# femtoBeacon_board_nRF52832_BT4_2_r1_0_0.net
KiCad netlist of a schematic drawn in EAGLE
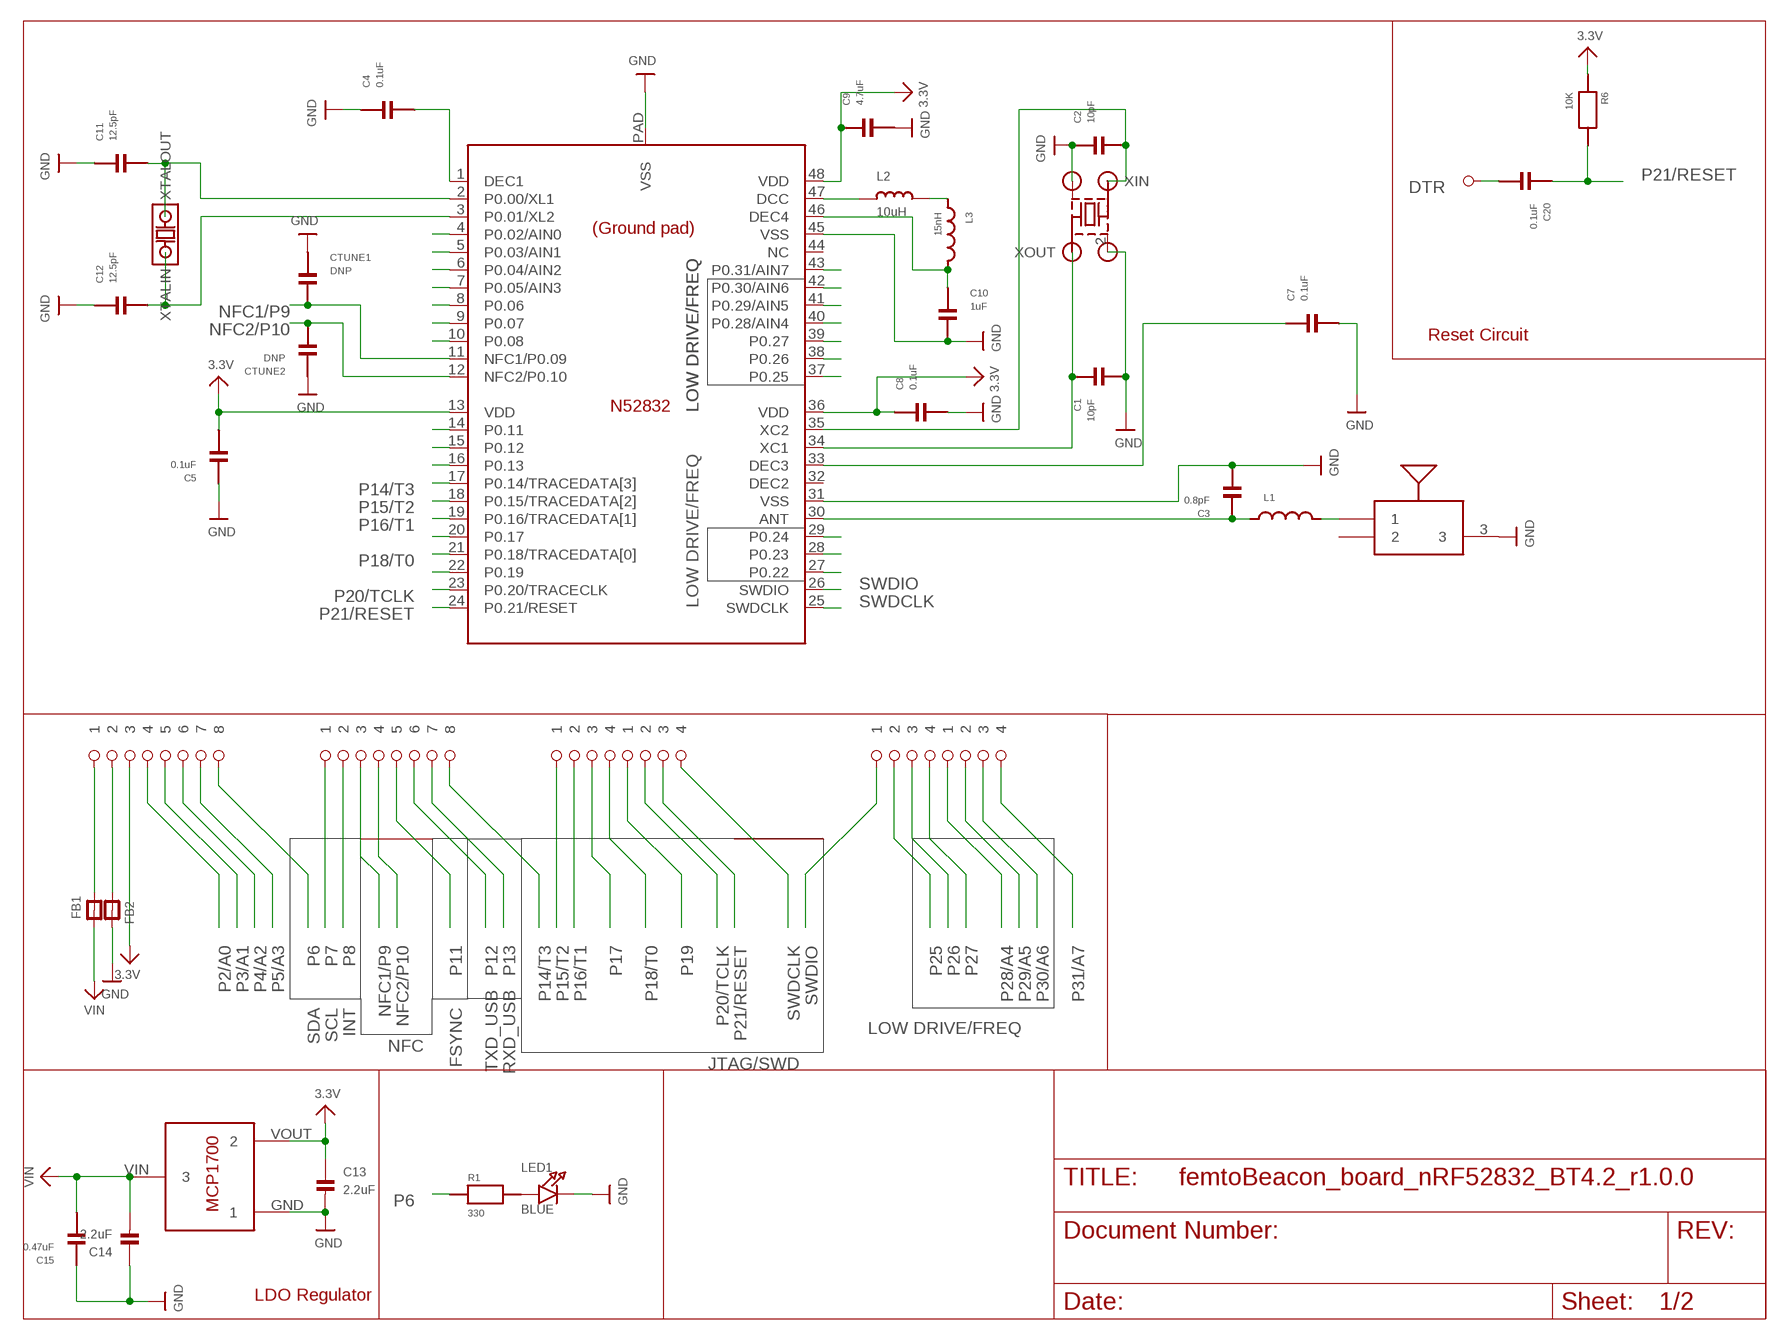
[diagram p0: schematic, sheet 1]
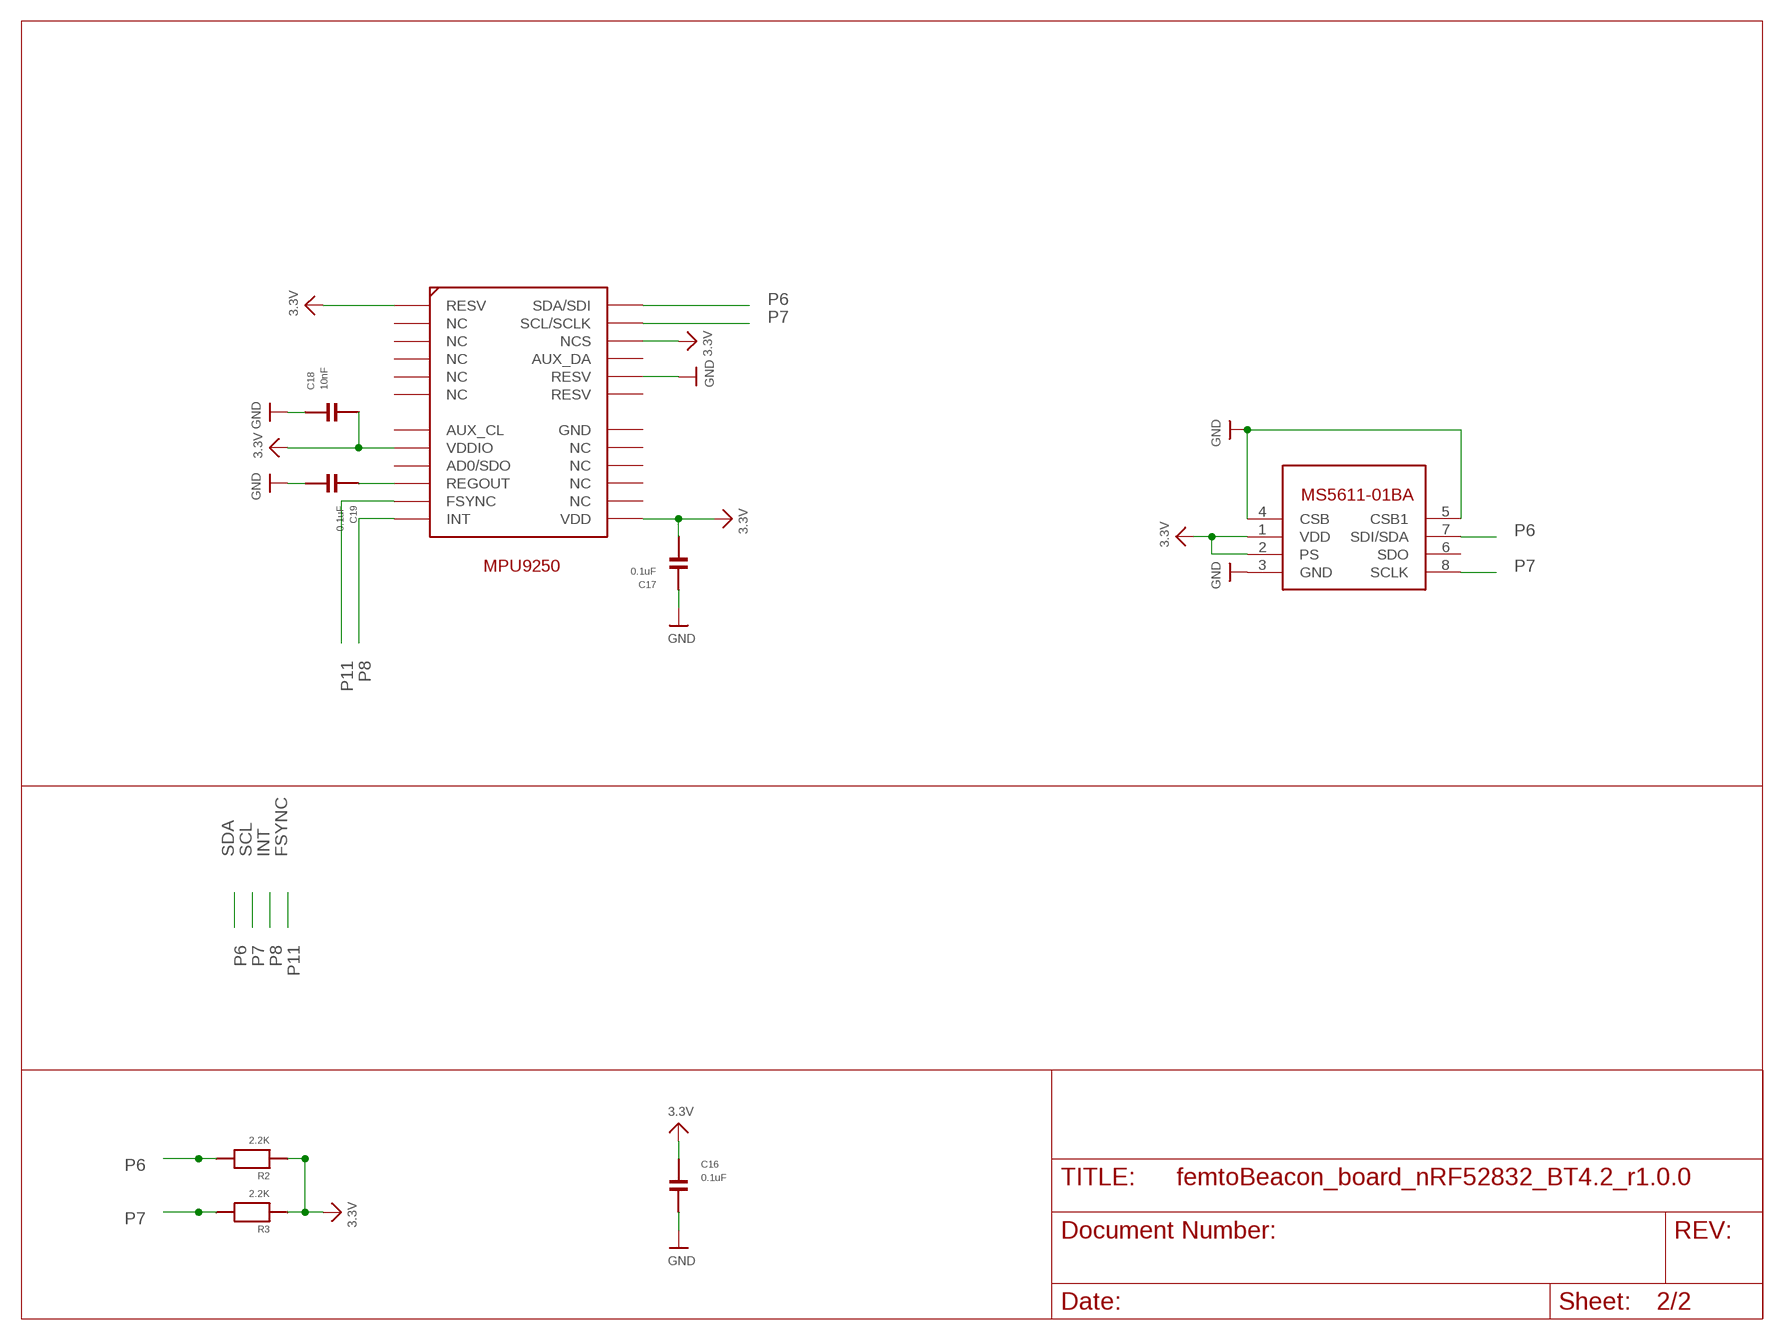
[diagram p1: schematic, sheet 2]

(export (version "E")
  (design (tool "Eeschema 10.0.6"))
  (components
    (comp (ref "BARO1")
      (value "MS5611-01BA03")
      (footprint "eagle-import:MS5611-01BA03")
      (libsource (lib "eagle-import") (part "MS5611-01BA03"))
    )
    (comp (ref "C16")
      (value "0.1uF")
      (footprint "eagle-import:PART")
      (libsource (lib "eagle-import") (part "CAPACITOR_0201"))
    )
    (comp (ref "C17")
      (value "0.1uF")
      (footprint "eagle-import:PART")
      (libsource (lib "eagle-import") (part "CAPACITOR_0201"))
    )
    (comp (ref "C18")
      (value "10nF")
      (footprint "eagle-import:PART")
      (libsource (lib "eagle-import") (part "CAPACITOR_0201"))
    )
    (comp (ref "C19")
      (value "0.1uF")
      (footprint "eagle-import:PART")
      (libsource (lib "eagle-import") (part "CAPACITOR_0201"))
    )
    (comp (ref "IMU1")
      (value "MPU-9250")
      (footprint "eagle-import:QFN_3X3MM")
      (libsource (lib "eagle-import") (part "MPU-9250"))
    )
    (comp (ref "R2")
      (value "2.2K")
      (footprint "eagle-import:PART")
      (libsource (lib "eagle-import") (part "RESISTOR_0201"))
    )
    (comp (ref "R3")
      (value "2.2K")
      (footprint "eagle-import:PART")
      (libsource (lib "eagle-import") (part "RESISTOR_0201"))
    )
    (comp (ref "ANTBAR")
      (value "PULSE_ANT_2.4GHZ")
      (footprint "eagle-import:ANT_BAR")
      (libsource (lib "eagle-import") (part "PULSE_ANT_2.4GHZ"))
    )
    (comp (ref "C1")
      (value "10pF")
      (footprint "eagle-import:PART")
      (libsource (lib "eagle-import") (part "CAPACITOR_0201"))
    )
    (comp (ref "C2")
      (value "10pF")
      (footprint "eagle-import:PART")
      (libsource (lib "eagle-import") (part "CAPACITOR_0201"))
    )
    (comp (ref "C3")
      (value "0.8pF")
      (footprint "eagle-import:PART")
      (libsource (lib "eagle-import") (part "CAPACITOR_0201"))
    )
    (comp (ref "C4")
      (value "0.1uF")
      (footprint "eagle-import:PART")
      (libsource (lib "eagle-import") (part "CAPACITOR_0201"))
    )
    (comp (ref "C5")
      (value "0.1uF")
      (footprint "eagle-import:PART")
      (libsource (lib "eagle-import") (part "CAPACITOR_0201"))
    )
    (comp (ref "C7")
      (value "0.1uF")
      (footprint "eagle-import:PART")
      (libsource (lib "eagle-import") (part "CAPACITOR_0201"))
    )
    (comp (ref "C8")
      (value "0.1uF")
      (footprint "eagle-import:PART")
      (libsource (lib "eagle-import") (part "CAPACITOR_0201"))
    )
    (comp (ref "C9")
      (value "4.7uF")
      (footprint "eagle-import:PART")
      (libsource (lib "eagle-import") (part "CAPACITOR_0201"))
    )
    (comp (ref "C10")
      (value "1uF")
      (footprint "eagle-import:PART")
      (libsource (lib "eagle-import") (part "CAPACITOR_0201"))
    )
    (comp (ref "C11")
      (value "12.5pF")
      (footprint "eagle-import:PART")
      (libsource (lib "eagle-import") (part "CAPACITOR_0201"))
    )
    (comp (ref "C12")
      (value "12.5pF")
      (footprint "eagle-import:PART")
      (libsource (lib "eagle-import") (part "CAPACITOR_0201"))
    )
    (comp (ref "C13")
      (value "2.2uF")
      (footprint "eagle-import:_0402MP")
      (libsource (lib "eagle-import") (part "CAP_CERAMIC_0402MP"))
    )
    (comp (ref "C14")
      (value "2.2uF")
      (footprint "eagle-import:_0402MP")
      (libsource (lib "eagle-import") (part "CAP_CERAMIC_0402MP"))
    )
    (comp (ref "C15")
      (value "0.47uF")
      (footprint "eagle-import:PART")
      (libsource (lib "eagle-import") (part "CAPACITOR_0201"))
    )
    (comp (ref "C20")
      (value "0.1uF")
      (footprint "eagle-import:PART")
      (libsource (lib "eagle-import") (part "CAPACITOR_0201"))
    )
    (comp (ref "CTUNE1")
      (value "DNP")
      (footprint "eagle-import:PART")
      (libsource (lib "eagle-import") (part "CAPACITOR_0201"))
    )
    (comp (ref "CTUNE2")
      (value "DNP")
      (footprint "eagle-import:PART")
      (libsource (lib "eagle-import") (part "CAPACITOR_0201"))
    )
    (comp (ref "FB1")
      (value "FERRITE_0603MP")
      (footprint "eagle-import:_0603MP")
      (libsource (lib "eagle-import") (part "FERRITE_0603MP"))
    )
    (comp (ref "FB2")
      (value "FERRITE_0603MP")
      (footprint "eagle-import:_0603MP")
      (libsource (lib "eagle-import") (part "FERRITE_0603MP"))
    )
    (comp (ref "IC1")
      (value "NRF52832_QFN48")
      (footprint "eagle-import:QFN48")
      (libsource (lib "eagle-import") (part "NRF52832_QFN48"))
    )
    (comp (ref "L1")
      (value "INDUCTOR_FIXED_0201")
      (footprint "eagle-import:PART")
      (libsource (lib "eagle-import") (part "INDUCTOR_FIXED_0201"))
    )
    (comp (ref "L2")
      (value "10uH")
      (footprint "eagle-import:_0603MP")
      (libsource (lib "eagle-import") (part "INDUCTOR_0603MP"))
    )
    (comp (ref "L3")
      (value "15nH")
      (footprint "eagle-import:PART")
      (libsource (lib "eagle-import") (part "INDUCTOR_FIXED_0201"))
    )
    (comp (ref "LED1")
      (value "BLUE")
      (footprint "eagle-import:CHIPLED_0603_NOOUTLINE")
      (libsource (lib "eagle-import") (part "LED0603_NOOUTLINE"))
    )
    (comp (ref "PIN4")
      (value "1X1_ROUND")
      (footprint "eagle-import:1X1_ROUND")
      (libsource (lib "eagle-import") (part "1X1_ROUND"))
    )
    (comp (ref "PINS1")
      (value "1X8_ROUND")
      (footprint "eagle-import:1X8_ROUND")
      (libsource (lib "eagle-import") (part "1X8_ROUND"))
    )
    (comp (ref "PINS2")
      (value "1X8_ROUND")
      (footprint "eagle-import:1X8_ROUND")
      (libsource (lib "eagle-import") (part "1X8_ROUND"))
    )
    (comp (ref "PINS3A")
      (value "1X4_ROUND")
      (footprint "eagle-import:1X4_ROUND")
      (libsource (lib "eagle-import") (part "1X4_ROUND"))
    )
    (comp (ref "PINS3B")
      (value "1X4_ROUND")
      (footprint "eagle-import:1X4_ROUND")
      (libsource (lib "eagle-import") (part "1X4_ROUND"))
    )
    (comp (ref "PINS4A")
      (value "1X4_ROUND")
      (footprint "eagle-import:1X4_ROUND")
      (libsource (lib "eagle-import") (part "1X4_ROUND"))
    )
    (comp (ref "PINS4B")
      (value "1X4_ROUND")
      (footprint "eagle-import:1X4_ROUND")
      (libsource (lib "eagle-import") (part "1X4_ROUND"))
    )
    (comp (ref "R1")
      (value "330")
      (footprint "eagle-import:PART")
      (libsource (lib "eagle-import") (part "RESISTOR_0201"))
    )
    (comp (ref "R6")
      (value "10K")
      (footprint "eagle-import:PART")
      (libsource (lib "eagle-import") (part "RESISTOR_0201"))
    )
    (comp (ref "U$4")
      (value "MCP1700T-3302E/TT")
      (footprint "eagle-import:MCP1700T-3302E_TT")
      (libsource (lib "eagle-import") (part "MCP1700T-3302E/TT"))
    )
    (comp (ref "U$53")
      (value "ABS06-107-32.768KHZ-T")
      (footprint "eagle-import:ABS06-107-32.768KHZ-T")
      (libsource (lib "eagle-import") (part "ABS06-107-32.768KHZ-T"))
    )
    (comp (ref "XTAL")
      (value "32MHz")
      (footprint "eagle-import:ABM11")
      (libsource (lib "eagle-import") (part "ABM11-32.000MHZ-D2X-T3"))
    )
  )
  (nets
    (net (code "1") (name "3.3V") (class "Default")
      (node (ref "BARO1") (pin "1") (pinfunction "VDD_1") (pintype "bidirectional"))
      (node (ref "BARO1") (pin "2") (pinfunction "PS_2") (pintype "bidirectional"))
      (node (ref "C13") (pin "1") (pinfunction "P$1_1") (pintype "passive"))
      (node (ref "C16") (pin "1") (pinfunction "P$1_1") (pintype "bidirectional"))
      (node (ref "C17") (pin "2") (pinfunction "P$2_2") (pintype "bidirectional"))
      (node (ref "C18") (pin "2") (pinfunction "P$2_2") (pintype "bidirectional"))
      (node (ref "C5") (pin "2") (pinfunction "P$2_2") (pintype "bidirectional"))
      (node (ref "C8") (pin "1") (pinfunction "P$1_1") (pintype "bidirectional"))
      (node (ref "C9") (pin "1") (pinfunction "P$1_1") (pintype "bidirectional"))
      (node (ref "IC1") (pin "13") (pinfunction "VDD_13") (pintype "bidirectional"))
      (node (ref "IC1") (pin "36") (pinfunction "VDD_36") (pintype "bidirectional"))
      (node (ref "IC1") (pin "48") (pinfunction "VDD_48") (pintype "bidirectional"))
      (node (ref "IMU1") (pin "P$1") (pinfunction "RESV_P$1") (pintype "bidirectional"))
      (node (ref "IMU1") (pin "P$13") (pinfunction "VDD_P$13") (pintype "bidirectional"))
      (node (ref "IMU1") (pin "P$22") (pinfunction "NCS_P$22") (pintype "bidirectional"))
      (node (ref "IMU1") (pin "P$8") (pinfunction "VDDIO_P$8") (pintype "bidirectional"))
      (node (ref "PINS1") (pin "P$3") (pinfunction "3_P$3") (pintype "bidirectional"))
      (node (ref "R2") (pin "1") (pinfunction "1_1") (pintype "bidirectional"))
      (node (ref "R3") (pin "1") (pinfunction "1_1") (pintype "bidirectional"))
      (node (ref "R6") (pin "1") (pinfunction "1_1") (pintype "bidirectional"))
      (node (ref "U$4") (pin "VOUT") (pinfunction "2_VOUT") (pintype "bidirectional"))
    )
    (net (code "2") (name "DTR") (class "Default")
      (node (ref "C20") (pin "2") (pinfunction "P$2_2") (pintype "bidirectional"))
      (node (ref "PIN4") (pin "P$1") (pinfunction "1_P$1") (pintype "bidirectional"))
    )
    (net (code "3") (name "GND") (class "Default")
      (node (ref "ANTBAR") (pin "3") (pinfunction "3_3") (pintype "bidirectional"))
      (node (ref "BARO1") (pin "3") (pinfunction "GND_3") (pintype "bidirectional"))
      (node (ref "BARO1") (pin "4") (pinfunction "CSB_4") (pintype "bidirectional"))
      (node (ref "BARO1") (pin "5") (pinfunction "CSB1_5") (pintype "bidirectional"))
      (node (ref "C1") (pin "2") (pinfunction "P$2_2") (pintype "bidirectional"))
      (node (ref "C10") (pin "2") (pinfunction "P$2_2") (pintype "bidirectional"))
      (node (ref "C11") (pin "1") (pinfunction "P$1_1") (pintype "bidirectional"))
      (node (ref "C12") (pin "1") (pinfunction "P$1_1") (pintype "bidirectional"))
      (node (ref "C13") (pin "2") (pinfunction "P$2_2") (pintype "passive"))
      (node (ref "C14") (pin "1") (pinfunction "P$1_1") (pintype "passive"))
      (node (ref "C15") (pin "1") (pinfunction "P$1_1") (pintype "bidirectional"))
      (node (ref "C16") (pin "2") (pinfunction "P$2_2") (pintype "bidirectional"))
      (node (ref "C17") (pin "1") (pinfunction "P$1_1") (pintype "bidirectional"))
      (node (ref "C18") (pin "1") (pinfunction "P$1_1") (pintype "bidirectional"))
      (node (ref "C19") (pin "2") (pinfunction "P$2_2") (pintype "bidirectional"))
      (node (ref "C2") (pin "1") (pinfunction "P$1_1") (pintype "bidirectional"))
      (node (ref "C3") (pin "2") (pinfunction "P$2_2") (pintype "bidirectional"))
      (node (ref "C4") (pin "1") (pinfunction "P$1_1") (pintype "bidirectional"))
      (node (ref "C5") (pin "1") (pinfunction "P$1_1") (pintype "bidirectional"))
      (node (ref "C7") (pin "2") (pinfunction "P$2_2") (pintype "bidirectional"))
      (node (ref "C8") (pin "2") (pinfunction "P$2_2") (pintype "bidirectional"))
      (node (ref "C9") (pin "2") (pinfunction "P$2_2") (pintype "bidirectional"))
      (node (ref "CTUNE1") (pin "1") (pinfunction "P$1_1") (pintype "bidirectional"))
      (node (ref "CTUNE2") (pin "1") (pinfunction "P$1_1") (pintype "bidirectional"))
      (node (ref "FB2") (pin "2") (pinfunction "P$2_2") (pintype "passive"))
      (node (ref "IC1") (pin "31") (pinfunction "VSS_31") (pintype "bidirectional"))
      (node (ref "IC1") (pin "45") (pinfunction "VSS_45") (pintype "bidirectional"))
      (node (ref "IC1") (pin "PAD") (pinfunction "VSS_PAD") (pintype "bidirectional"))
      (node (ref "IMU1") (pin "P$20") (pinfunction "RESV_P$20") (pintype "bidirectional"))
      (node (ref "LED1") (pin "C") (pinfunction "C_C") (pintype "passive"))
      (node (ref "U$4") (pin "GND") (pinfunction "1_GND") (pintype "bidirectional"))
      (node (ref "XTAL") (pin "2") (pinfunction "GND_2") (pintype "bidirectional"))
      (node (ref "XTAL") (pin "4") (pinfunction "GND_4") (pintype "bidirectional"))
    )
    (net (code "4") (name "NFC1{slash}P9") (class "Default")
      (node (ref "CTUNE1") (pin "2") (pinfunction "P$2_2") (pintype "bidirectional"))
      (node (ref "IC1") (pin "11") (pinfunction "NFC1/P0.09_11") (pintype "bidirectional"))
      (node (ref "PINS2") (pin "P$3") (pinfunction "3_P$3") (pintype "bidirectional"))
    )
    (net (code "5") (name "NFC2{slash}P10") (class "Default")
      (node (ref "CTUNE2") (pin "2") (pinfunction "P$2_2") (pintype "bidirectional"))
      (node (ref "IC1") (pin "12") (pinfunction "NFC2/P0.10_12") (pintype "bidirectional"))
      (node (ref "PINS2") (pin "P$4") (pinfunction "4_P$4") (pintype "bidirectional"))
    )
    (net (code "6") (name "Net-(C1-P$1)") (class "Default")
      (node (ref "C1") (pin "1") (pinfunction "P$1_1") (pintype "bidirectional"))
      (node (ref "IC1") (pin "34") (pinfunction "XC1_34") (pintype "bidirectional"))
      (node (ref "XTAL") (pin "3") (pinfunction "XOUT_3") (pintype "bidirectional"))
    )
    (net (code "7") (name "Net-(C2-P$2)") (class "Default")
      (node (ref "C2") (pin "2") (pinfunction "P$2_2") (pintype "bidirectional"))
      (node (ref "IC1") (pin "35") (pinfunction "XC2_35") (pintype "bidirectional"))
      (node (ref "XTAL") (pin "1") (pinfunction "XIN_1") (pintype "bidirectional"))
    )
    (net (code "8") (name "Net-(C3-P$1)") (class "Default")
      (node (ref "C3") (pin "1") (pinfunction "P$1_1") (pintype "bidirectional"))
      (node (ref "IC1") (pin "30") (pinfunction "ANT_30") (pintype "bidirectional"))
      (node (ref "L1") (pin "1") (pinfunction "P$1_1") (pintype "bidirectional"))
    )
    (net (code "9") (name "Net-(C4-P$2)") (class "Default")
      (node (ref "C4") (pin "2") (pinfunction "P$2_2") (pintype "bidirectional"))
      (node (ref "IC1") (pin "1") (pinfunction "DEC1_1") (pintype "bidirectional"))
    )
    (net (code "10") (name "Net-(C7-P$1)") (class "Default")
      (node (ref "C7") (pin "1") (pinfunction "P$1_1") (pintype "bidirectional"))
      (node (ref "IC1") (pin "33") (pinfunction "DEC3_33") (pintype "bidirectional"))
    )
    (net (code "11") (name "Net-(C10-P$1)") (class "Default")
      (node (ref "C10") (pin "1") (pinfunction "P$1_1") (pintype "bidirectional"))
      (node (ref "IC1") (pin "46") (pinfunction "DEC4_46") (pintype "bidirectional"))
      (node (ref "L3") (pin "2") (pinfunction "P$2_2") (pintype "bidirectional"))
    )
    (net (code "12") (name "Net-(C11-P$2)") (class "Default")
      (node (ref "C11") (pin "2") (pinfunction "P$2_2") (pintype "bidirectional"))
      (node (ref "IC1") (pin "2") (pinfunction "P0.00/XL1_2") (pintype "bidirectional"))
      (node (ref "U$53") (pin "2") (pinfunction "XTALOUT_2") (pintype "bidirectional"))
    )
    (net (code "13") (name "Net-(C12-P$2)") (class "Default")
      (node (ref "C12") (pin "2") (pinfunction "P$2_2") (pintype "bidirectional"))
      (node (ref "IC1") (pin "3") (pinfunction "P0.01/XL2_3") (pintype "bidirectional"))
      (node (ref "U$53") (pin "1") (pinfunction "XTALIN_1") (pintype "bidirectional"))
    )
    (net (code "14") (name "Net-(C19-P$1)") (class "Default")
      (node (ref "C19") (pin "1") (pinfunction "P$1_1") (pintype "bidirectional"))
      (node (ref "IMU1") (pin "P$10") (pinfunction "REGOUT_P$10") (pintype "bidirectional"))
    )
    (net (code "15") (name "Net-(FB1-P$2)") (class "Default")
      (node (ref "FB1") (pin "2") (pinfunction "P$2_2") (pintype "passive"))
      (node (ref "PINS1") (pin "P$1") (pinfunction "1_P$1") (pintype "bidirectional"))
    )
    (net (code "16") (name "Net-(FB2-P$1)") (class "Default")
      (node (ref "FB2") (pin "1") (pinfunction "P$1_1") (pintype "passive"))
      (node (ref "PINS1") (pin "P$2") (pinfunction "2_P$2") (pintype "bidirectional"))
    )
    (net (code "17") (name "Net-(IC1-DCC)") (class "Default")
      (node (ref "IC1") (pin "47") (pinfunction "DCC_47") (pintype "bidirectional"))
      (node (ref "L2") (pin "1") (pinfunction "1_1") (pintype "passive"))
    )
    (net (code "18") (name "Net-(L1-P$2)") (class "Default")
      (node (ref "ANTBAR") (pin "1") (pinfunction "1_1") (pintype "bidirectional"))
      (node (ref "L1") (pin "2") (pinfunction "P$2_2") (pintype "bidirectional"))
    )
    (net (code "19") (name "Net-(L3-P$1)") (class "Default")
      (node (ref "L2") (pin "2") (pinfunction "2_2") (pintype "passive"))
      (node (ref "L3") (pin "1") (pinfunction "P$1_1") (pintype "bidirectional"))
    )
    (net (code "20") (name "Net-(LED1-PadA)") (class "Default")
      (node (ref "LED1") (pin "A") (pinfunction "A_A") (pintype "passive"))
      (node (ref "R1") (pin "2") (pinfunction "2_2") (pintype "bidirectional"))
    )
    (net (code "21") (name "P2{slash}A0") (class "Default")
      (node (ref "IC1") (pin "4") (pinfunction "P0.02/AIN0_4") (pintype "bidirectional"))
      (node (ref "PINS1") (pin "P$4") (pinfunction "4_P$4") (pintype "bidirectional"))
    )
    (net (code "22") (name "P3{slash}A1") (class "Default")
      (node (ref "IC1") (pin "5") (pinfunction "P0.03/AIN1_5") (pintype "bidirectional"))
      (node (ref "PINS1") (pin "P$5") (pinfunction "5_P$5") (pintype "bidirectional"))
    )
    (net (code "23") (name "P4{slash}A2") (class "Default")
      (node (ref "IC1") (pin "6") (pinfunction "P0.04/AIN2_6") (pintype "bidirectional"))
      (node (ref "PINS1") (pin "P$6") (pinfunction "6_P$6") (pintype "bidirectional"))
    )
    (net (code "24") (name "P5{slash}A3") (class "Default")
      (node (ref "IC1") (pin "7") (pinfunction "P0.05/AIN3_7") (pintype "bidirectional"))
      (node (ref "PINS1") (pin "P$7") (pinfunction "7_P$7") (pintype "bidirectional"))
    )
    (net (code "25") (name "P6") (class "Default")
      (node (ref "BARO1") (pin "7") (pinfunction "SDI/SDA_7") (pintype "bidirectional"))
      (node (ref "IC1") (pin "8") (pinfunction "P0.06_8") (pintype "bidirectional"))
      (node (ref "IMU1") (pin "P$24") (pinfunction "SDA/SDI_P$24") (pintype "bidirectional"))
      (node (ref "PINS1") (pin "P$8") (pinfunction "8_P$8") (pintype "bidirectional"))
      (node (ref "R1") (pin "1") (pinfunction "1_1") (pintype "bidirectional"))
      (node (ref "R2") (pin "2") (pinfunction "2_2") (pintype "bidirectional"))
    )
    (net (code "26") (name "P7") (class "Default")
      (node (ref "BARO1") (pin "8") (pinfunction "SCLK_8") (pintype "bidirectional"))
      (node (ref "IC1") (pin "9") (pinfunction "P0.07_9") (pintype "bidirectional"))
      (node (ref "IMU1") (pin "P$23") (pinfunction "SCL/SCLK_P$23") (pintype "bidirectional"))
      (node (ref "PINS2") (pin "P$1") (pinfunction "1_P$1") (pintype "bidirectional"))
      (node (ref "R3") (pin "2") (pinfunction "2_2") (pintype "bidirectional"))
    )
    (net (code "27") (name "P8") (class "Default")
      (node (ref "IC1") (pin "10") (pinfunction "P0.08_10") (pintype "bidirectional"))
      (node (ref "IMU1") (pin "P$12") (pinfunction "INT_P$12") (pintype "bidirectional"))
      (node (ref "PINS2") (pin "P$2") (pinfunction "2_P$2") (pintype "bidirectional"))
    )
    (net (code "28") (name "P11") (class "Default")
      (node (ref "IC1") (pin "14") (pinfunction "P0.11_14") (pintype "bidirectional"))
      (node (ref "IMU1") (pin "P$11") (pinfunction "FSYNC_P$11") (pintype "bidirectional"))
      (node (ref "PINS2") (pin "P$5") (pinfunction "5_P$5") (pintype "bidirectional"))
    )
    (net (code "29") (name "P12") (class "Default")
      (node (ref "IC1") (pin "15") (pinfunction "P0.12_15") (pintype "bidirectional"))
      (node (ref "PINS2") (pin "P$6") (pinfunction "6_P$6") (pintype "bidirectional"))
    )
    (net (code "30") (name "P13") (class "Default")
      (node (ref "IC1") (pin "16") (pinfunction "P0.13_16") (pintype "bidirectional"))
      (node (ref "PINS2") (pin "P$7") (pinfunction "7_P$7") (pintype "bidirectional"))
    )
    (net (code "31") (name "P14{slash}T3") (class "Default")
      (node (ref "IC1") (pin "17") (pinfunction "P0.14/TRACEDATA[3]_17") (pintype "bidirectional"))
      (node (ref "PINS2") (pin "P$8") (pinfunction "8_P$8") (pintype "bidirectional"))
    )
    (net (code "32") (name "P15{slash}T2") (class "Default")
      (node (ref "IC1") (pin "18") (pinfunction "P0.15/TRACEDATA[2]_18") (pintype "bidirectional"))
      (node (ref "PINS3A") (pin "P$1") (pinfunction "1_P$1") (pintype "bidirectional"))
    )
    (net (code "33") (name "P16{slash}T1") (class "Default")
      (node (ref "IC1") (pin "19") (pinfunction "P0.16/TRACEDATA[1]_19") (pintype "bidirectional"))
      (node (ref "PINS3A") (pin "P$2") (pinfunction "2_P$2") (pintype "bidirectional"))
    )
    (net (code "34") (name "P17") (class "Default")
      (node (ref "IC1") (pin "20") (pinfunction "P0.17_20") (pintype "bidirectional"))
      (node (ref "PINS3A") (pin "P$3") (pinfunction "3_P$3") (pintype "bidirectional"))
    )
    (net (code "35") (name "P18{slash}T0") (class "Default")
      (node (ref "IC1") (pin "21") (pinfunction "P0.18/TRACEDATA[0]_21") (pintype "bidirectional"))
      (node (ref "PINS3A") (pin "P$4") (pinfunction "4_P$4") (pintype "bidirectional"))
    )
    (net (code "36") (name "P19") (class "Default")
      (node (ref "IC1") (pin "22") (pinfunction "P0.19_22") (pintype "bidirectional"))
      (node (ref "PINS3B") (pin "P$1") (pinfunction "1_P$1") (pintype "bidirectional"))
    )
    (net (code "37") (name "P20{slash}TCLK") (class "Default")
      (node (ref "IC1") (pin "23") (pinfunction "P0.20/TRACECLK_23") (pintype "bidirectional"))
      (node (ref "PINS3B") (pin "P$2") (pinfunction "2_P$2") (pintype "bidirectional"))
    )
    (net (code "38") (name "P21{slash}RESET") (class "Default")
      (node (ref "C20") (pin "1") (pinfunction "P$1_1") (pintype "bidirectional"))
      (node (ref "IC1") (pin "24") (pinfunction "P0.21/RESET_24") (pintype "bidirectional"))
      (node (ref "PINS3B") (pin "P$3") (pinfunction "3_P$3") (pintype "bidirectional"))
      (node (ref "R6") (pin "2") (pinfunction "2_2") (pintype "bidirectional"))
    )
    (net (code "39") (name "P25") (class "Default")
      (node (ref "IC1") (pin "37") (pinfunction "P0.25_37") (pintype "bidirectional"))
      (node (ref "PINS4A") (pin "P$2") (pinfunction "2_P$2") (pintype "bidirectional"))
    )
    (net (code "40") (name "P26") (class "Default")
      (node (ref "IC1") (pin "38") (pinfunction "P0.26_38") (pintype "bidirectional"))
      (node (ref "PINS4A") (pin "P$3") (pinfunction "3_P$3") (pintype "bidirectional"))
    )
    (net (code "41") (name "P27") (class "Default")
      (node (ref "IC1") (pin "39") (pinfunction "P0.27_39") (pintype "bidirectional"))
      (node (ref "PINS4A") (pin "P$4") (pinfunction "4_P$4") (pintype "bidirectional"))
    )
    (net (code "42") (name "P28{slash}A4") (class "Default")
      (node (ref "IC1") (pin "40") (pinfunction "P0.28/AIN4_40") (pintype "bidirectional"))
      (node (ref "PINS4B") (pin "P$1") (pinfunction "1_P$1") (pintype "bidirectional"))
    )
    (net (code "43") (name "P29{slash}A5") (class "Default")
      (node (ref "IC1") (pin "41") (pinfunction "P0.29/AIN5_41") (pintype "bidirectional"))
      (node (ref "PINS4B") (pin "P$2") (pinfunction "2_P$2") (pintype "bidirectional"))
    )
    (net (code "44") (name "P30{slash}A6") (class "Default")
      (node (ref "IC1") (pin "42") (pinfunction "P0.30/AIN6_42") (pintype "bidirectional"))
      (node (ref "PINS4B") (pin "P$3") (pinfunction "3_P$3") (pintype "bidirectional"))
    )
    (net (code "45") (name "P31{slash}A7") (class "Default")
      (node (ref "IC1") (pin "43") (pinfunction "P0.31/AIN7_43") (pintype "bidirectional"))
      (node (ref "PINS4B") (pin "P$4") (pinfunction "4_P$4") (pintype "bidirectional"))
    )
    (net (code "46") (name "SWDCLK") (class "Default")
      (node (ref "IC1") (pin "25") (pinfunction "SWDCLK_25") (pintype "bidirectional"))
      (node (ref "PINS3B") (pin "P$4") (pinfunction "4_P$4") (pintype "bidirectional"))
    )
    (net (code "47") (name "SWDIO") (class "Default")
      (node (ref "IC1") (pin "26") (pinfunction "SWDIO_26") (pintype "bidirectional"))
      (node (ref "PINS4A") (pin "P$1") (pinfunction "1_P$1") (pintype "bidirectional"))
    )
    (net (code "48") (name "VIN") (class "Default")
      (node (ref "C14") (pin "2") (pinfunction "P$2_2") (pintype "passive"))
      (node (ref "C15") (pin "2") (pinfunction "P$2_2") (pintype "bidirectional"))
      (node (ref "FB1") (pin "1") (pinfunction "P$1_1") (pintype "passive"))
      (node (ref "U$4") (pin "VIN") (pinfunction "3_VIN") (pintype "bidirectional"))
    )
    (net (code "49") (name "unconnected-(ANTBAR-Pad2)") (class "Default")
      (node (ref "ANTBAR") (pin "2") (pinfunction "2_2") (pintype "bidirectional"))
    )
    (net (code "50") (name "unconnected-(BARO1-SDO-Pad6)") (class "Default")
      (node (ref "BARO1") (pin "6") (pinfunction "SDO_6") (pintype "bidirectional"))
    )
    (net (code "51") (name "unconnected-(IC1-DEC2-Pad32)") (class "Default")
      (node (ref "IC1") (pin "32") (pinfunction "DEC2_32") (pintype "bidirectional"))
    )
    (net (code "52") (name "unconnected-(IC1-NC-Pad44)") (class "Default")
      (node (ref "IC1") (pin "44") (pinfunction "NC_44") (pintype "bidirectional"))
    )
    (net (code "53") (name "unconnected-(IC1-P0.22-Pad27)") (class "Default")
      (node (ref "IC1") (pin "27") (pinfunction "P0.22_27") (pintype "bidirectional"))
    )
    (net (code "54") (name "unconnected-(IC1-P0.23-Pad28)") (class "Default")
      (node (ref "IC1") (pin "28") (pinfunction "P0.23_28") (pintype "bidirectional"))
    )
    (net (code "55") (name "unconnected-(IC1-P0.24-Pad29)") (class "Default")
      (node (ref "IC1") (pin "29") (pinfunction "P0.24_29") (pintype "bidirectional"))
    )
    (net (code "56") (name "unconnected-(IMU1-AD0{slash}SDO-PadP$9)") (class "Default")
      (node (ref "IMU1") (pin "P$9") (pinfunction "AD0/SDO_P$9") (pintype "bidirectional"))
    )
    (net (code "57") (name "unconnected-(IMU1-AUX_CL-PadP$7)") (class "Default")
      (node (ref "IMU1") (pin "P$7") (pinfunction "AUX_CL_P$7") (pintype "bidirectional"))
    )
    (net (code "58") (name "unconnected-(IMU1-AUX_DA-PadP$21)") (class "Default")
      (node (ref "IMU1") (pin "P$21") (pinfunction "AUX_DA_P$21") (pintype "bidirectional"))
    )
    (net (code "59") (name "unconnected-(IMU1-GND-PadP$18)") (class "Default")
      (node (ref "IMU1") (pin "P$18") (pinfunction "GND_P$18") (pintype "bidirectional"))
    )
    (net (code "60") (name "unconnected-(IMU1-NC-PadP$2)") (class "Default")
      (node (ref "IMU1") (pin "P$2") (pinfunction "NC_P$2") (pintype "bidirectional"))
    )
    (net (code "61") (name "unconnected-(IMU1-NC-PadP$3)") (class "Default")
      (node (ref "IMU1") (pin "P$3") (pinfunction "NC_P$3") (pintype "bidirectional"))
    )
    (net (code "62") (name "unconnected-(IMU1-NC-PadP$4)") (class "Default")
      (node (ref "IMU1") (pin "P$4") (pinfunction "NC_P$4") (pintype "bidirectional"))
    )
    (net (code "63") (name "unconnected-(IMU1-NC-PadP$5)") (class "Default")
      (node (ref "IMU1") (pin "P$5") (pinfunction "NC_P$5") (pintype "bidirectional"))
    )
    (net (code "64") (name "unconnected-(IMU1-NC-PadP$6)") (class "Default")
      (node (ref "IMU1") (pin "P$6") (pinfunction "NC_P$6") (pintype "bidirectional"))
    )
    (net (code "65") (name "unconnected-(IMU1-NC-PadP$14)") (class "Default")
      (node (ref "IMU1") (pin "P$14") (pinfunction "NC_P$14") (pintype "bidirectional"))
    )
    (net (code "66") (name "unconnected-(IMU1-NC-PadP$15)") (class "Default")
      (node (ref "IMU1") (pin "P$15") (pinfunction "NC_P$15") (pintype "bidirectional"))
    )
    (net (code "67") (name "unconnected-(IMU1-NC-PadP$16)") (class "Default")
      (node (ref "IMU1") (pin "P$16") (pinfunction "NC_P$16") (pintype "bidirectional"))
    )
    (net (code "68") (name "unconnected-(IMU1-NC-PadP$17)") (class "Default")
      (node (ref "IMU1") (pin "P$17") (pinfunction "NC_P$17") (pintype "bidirectional"))
    )
    (net (code "69") (name "unconnected-(IMU1-RESV-PadP$19)") (class "Default")
      (node (ref "IMU1") (pin "P$19") (pinfunction "RESV_P$19") (pintype "bidirectional"))
    )
  )
)
